# 6_Button_Array.net
KiCad netlist of a schematic drawn in EAGLE
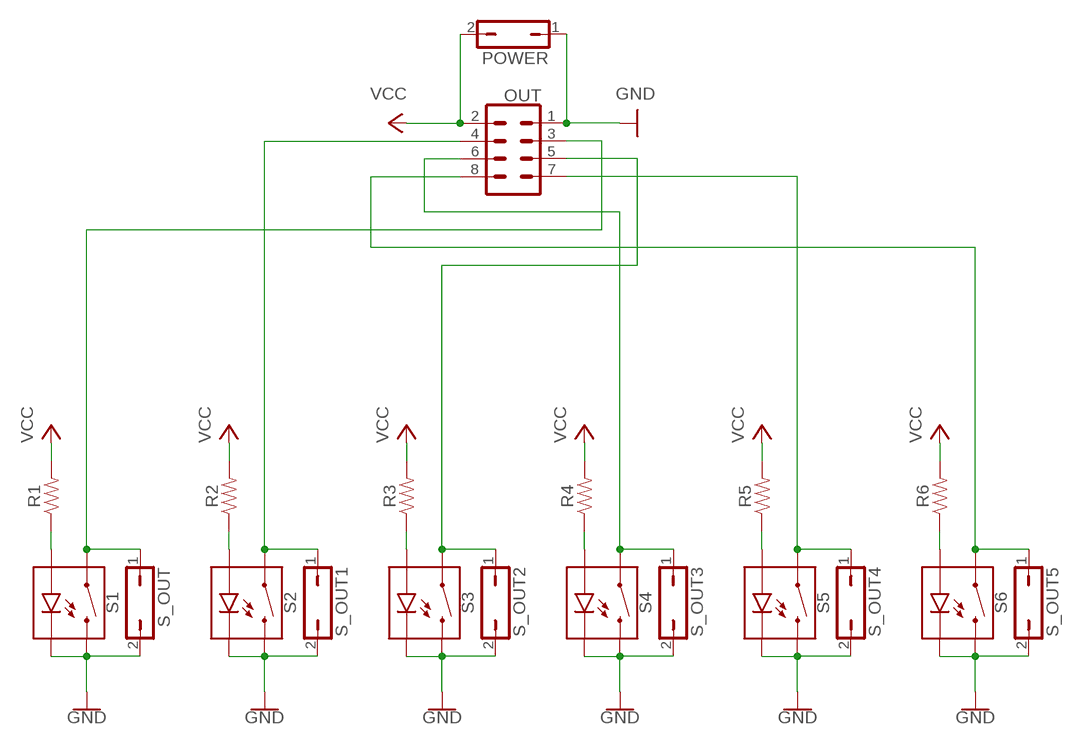
[diagram p0: schematic, sheet 1]

(export (version "E")
  (design (tool "Eeschema 10.0.6"))
  (components
    (comp (ref "OUT")
      (value "CONN_04X2")
      (footprint "eagle-import:2X4")
      (libsource (lib "eagle-import") (part "CONN_04X2"))
    )
    (comp (ref "POWER")
      (value "JP1Q")
      (footprint "eagle-import:JP1")
      (libsource (lib "eagle-import") (part "JP1Q"))
    )
    (comp (ref "R1")
      (value "RESISTOR1206")
      (footprint "eagle-import:1206")
      (libsource (lib "eagle-import") (part "RESISTOR1206"))
    )
    (comp (ref "R2")
      (value "RESISTOR1206")
      (footprint "eagle-import:1206")
      (libsource (lib "eagle-import") (part "RESISTOR1206"))
    )
    (comp (ref "R3")
      (value "RESISTOR1206")
      (footprint "eagle-import:1206")
      (libsource (lib "eagle-import") (part "RESISTOR1206"))
    )
    (comp (ref "R4")
      (value "RESISTOR1206")
      (footprint "eagle-import:1206")
      (libsource (lib "eagle-import") (part "RESISTOR1206"))
    )
    (comp (ref "R5")
      (value "RESISTOR1206")
      (footprint "eagle-import:1206")
      (libsource (lib "eagle-import") (part "RESISTOR1206"))
    )
    (comp (ref "R6")
      (value "RESISTOR1206")
      (footprint "eagle-import:1206")
      (libsource (lib "eagle-import") (part "RESISTOR1206"))
    )
    (comp (ref "S1")
      (value "MOMENTARY-SWITCH-SPST-LED-PTH-12MM")
      (footprint "eagle-import:TACTILE_SWITCH_LED_PTH_12MM")
      (libsource (lib "eagle-import") (part "MOMENTARY-SWITCH-SPST-LED-PTH-12MM"))
    )
    (comp (ref "S2")
      (value "MOMENTARY-SWITCH-SPST-LED-PTH-12MM")
      (footprint "eagle-import:TACTILE_SWITCH_LED_PTH_12MM")
      (libsource (lib "eagle-import") (part "MOMENTARY-SWITCH-SPST-LED-PTH-12MM"))
    )
    (comp (ref "S3")
      (value "MOMENTARY-SWITCH-SPST-LED-PTH-12MM")
      (footprint "eagle-import:TACTILE_SWITCH_LED_PTH_12MM")
      (libsource (lib "eagle-import") (part "MOMENTARY-SWITCH-SPST-LED-PTH-12MM"))
    )
    (comp (ref "S4")
      (value "MOMENTARY-SWITCH-SPST-LED-PTH-12MM")
      (footprint "eagle-import:TACTILE_SWITCH_LED_PTH_12MM")
      (libsource (lib "eagle-import") (part "MOMENTARY-SWITCH-SPST-LED-PTH-12MM"))
    )
    (comp (ref "S5")
      (value "MOMENTARY-SWITCH-SPST-LED-PTH-12MM")
      (footprint "eagle-import:TACTILE_SWITCH_LED_PTH_12MM")
      (libsource (lib "eagle-import") (part "MOMENTARY-SWITCH-SPST-LED-PTH-12MM"))
    )
    (comp (ref "S6")
      (value "MOMENTARY-SWITCH-SPST-LED-PTH-12MM")
      (footprint "eagle-import:TACTILE_SWITCH_LED_PTH_12MM")
      (libsource (lib "eagle-import") (part "MOMENTARY-SWITCH-SPST-LED-PTH-12MM"))
    )
    (comp (ref "S_OUT")
      (value "JP1Q")
      (footprint "eagle-import:JP1")
      (libsource (lib "eagle-import") (part "JP1Q"))
    )
    (comp (ref "S_OUT1")
      (value "JP1Q")
      (footprint "eagle-import:JP1")
      (libsource (lib "eagle-import") (part "JP1Q"))
    )
    (comp (ref "S_OUT2")
      (value "JP1Q")
      (footprint "eagle-import:JP1")
      (libsource (lib "eagle-import") (part "JP1Q"))
    )
    (comp (ref "S_OUT3")
      (value "JP1Q")
      (footprint "eagle-import:JP1")
      (libsource (lib "eagle-import") (part "JP1Q"))
    )
    (comp (ref "S_OUT4")
      (value "JP1Q")
      (footprint "eagle-import:JP1")
      (libsource (lib "eagle-import") (part "JP1Q"))
    )
    (comp (ref "S_OUT5")
      (value "JP1Q")
      (footprint "eagle-import:JP1")
      (libsource (lib "eagle-import") (part "JP1Q"))
    )
  )
  (nets
    (net (code "1") (name "GND") (class "Default")
      (node (ref "OUT") (pin "1") (pinfunction "1_1") (pintype "passive"))
      (node (ref "POWER") (pin "1") (pinfunction "1_1") (pintype "passive"))
      (node (ref "S1") (pin "2") (pinfunction "2_2") (pintype "passive"))
      (node (ref "S1") (pin "C") (pinfunction "C_C") (pintype "passive"))
      (node (ref "S2") (pin "2") (pinfunction "2_2") (pintype "passive"))
      (node (ref "S2") (pin "C") (pinfunction "C_C") (pintype "passive"))
      (node (ref "S3") (pin "2") (pinfunction "2_2") (pintype "passive"))
      (node (ref "S3") (pin "C") (pinfunction "C_C") (pintype "passive"))
      (node (ref "S4") (pin "2") (pinfunction "2_2") (pintype "passive"))
      (node (ref "S4") (pin "C") (pinfunction "C_C") (pintype "passive"))
      (node (ref "S5") (pin "2") (pinfunction "2_2") (pintype "passive"))
      (node (ref "S5") (pin "C") (pinfunction "C_C") (pintype "passive"))
      (node (ref "S6") (pin "2") (pinfunction "2_2") (pintype "passive"))
      (node (ref "S6") (pin "C") (pinfunction "C_C") (pintype "passive"))
      (node (ref "S_OUT") (pin "2") (pinfunction "2_2") (pintype "passive"))
      (node (ref "S_OUT1") (pin "2") (pinfunction "2_2") (pintype "passive"))
      (node (ref "S_OUT2") (pin "2") (pinfunction "2_2") (pintype "passive"))
      (node (ref "S_OUT3") (pin "2") (pinfunction "2_2") (pintype "passive"))
      (node (ref "S_OUT4") (pin "2") (pinfunction "2_2") (pintype "passive"))
      (node (ref "S_OUT5") (pin "2") (pinfunction "2_2") (pintype "passive"))
    )
    (net (code "2") (name "Net-(R1-Pad1)") (class "Default")
      (node (ref "R1") (pin "1") (pinfunction "1_1") (pintype "passive"))
      (node (ref "S1") (pin "A") (pinfunction "A_A") (pintype "passive"))
    )
    (net (code "3") (name "Net-(R2-Pad1)") (class "Default")
      (node (ref "R2") (pin "1") (pinfunction "1_1") (pintype "passive"))
      (node (ref "S2") (pin "A") (pinfunction "A_A") (pintype "passive"))
    )
    (net (code "4") (name "Net-(R3-Pad1)") (class "Default")
      (node (ref "R3") (pin "1") (pinfunction "1_1") (pintype "passive"))
      (node (ref "S3") (pin "A") (pinfunction "A_A") (pintype "passive"))
    )
    (net (code "5") (name "Net-(R4-Pad1)") (class "Default")
      (node (ref "R4") (pin "1") (pinfunction "1_1") (pintype "passive"))
      (node (ref "S4") (pin "A") (pinfunction "A_A") (pintype "passive"))
    )
    (net (code "6") (name "Net-(R5-Pad1)") (class "Default")
      (node (ref "R5") (pin "1") (pinfunction "1_1") (pintype "passive"))
      (node (ref "S5") (pin "A") (pinfunction "A_A") (pintype "passive"))
    )
    (net (code "7") (name "Net-(R6-Pad1)") (class "Default")
      (node (ref "R6") (pin "1") (pinfunction "1_1") (pintype "passive"))
      (node (ref "S6") (pin "A") (pinfunction "A_A") (pintype "passive"))
    )
    (net (code "8") (name "Net-(S1-1)") (class "Default")
      (node (ref "OUT") (pin "3") (pinfunction "3_3") (pintype "passive"))
      (node (ref "S1") (pin "4") (pinfunction "1_4") (pintype "passive"))
      (node (ref "S_OUT") (pin "1") (pinfunction "1_1") (pintype "passive"))
    )
    (net (code "9") (name "Net-(S2-1)") (class "Default")
      (node (ref "OUT") (pin "4") (pinfunction "4_4") (pintype "passive"))
      (node (ref "S2") (pin "4") (pinfunction "1_4") (pintype "passive"))
      (node (ref "S_OUT1") (pin "1") (pinfunction "1_1") (pintype "passive"))
    )
    (net (code "10") (name "Net-(S3-1)") (class "Default")
      (node (ref "OUT") (pin "5") (pinfunction "5_5") (pintype "passive"))
      (node (ref "S3") (pin "4") (pinfunction "1_4") (pintype "passive"))
      (node (ref "S_OUT2") (pin "1") (pinfunction "1_1") (pintype "passive"))
    )
    (net (code "11") (name "Net-(S4-1)") (class "Default")
      (node (ref "OUT") (pin "6") (pinfunction "6_6") (pintype "passive"))
      (node (ref "S4") (pin "4") (pinfunction "1_4") (pintype "passive"))
      (node (ref "S_OUT3") (pin "1") (pinfunction "1_1") (pintype "passive"))
    )
    (net (code "12") (name "Net-(S5-1)") (class "Default")
      (node (ref "OUT") (pin "7") (pinfunction "7_7") (pintype "passive"))
      (node (ref "S5") (pin "4") (pinfunction "1_4") (pintype "passive"))
      (node (ref "S_OUT4") (pin "1") (pinfunction "1_1") (pintype "passive"))
    )
    (net (code "13") (name "Net-(S6-1)") (class "Default")
      (node (ref "OUT") (pin "8") (pinfunction "8_8") (pintype "passive"))
      (node (ref "S6") (pin "4") (pinfunction "1_4") (pintype "passive"))
      (node (ref "S_OUT5") (pin "1") (pinfunction "1_1") (pintype "passive"))
    )
    (net (code "14") (name "VCC") (class "Default")
      (node (ref "OUT") (pin "2") (pinfunction "2_2") (pintype "passive"))
      (node (ref "POWER") (pin "2") (pinfunction "2_2") (pintype "passive"))
      (node (ref "R1") (pin "2") (pinfunction "2_2") (pintype "passive"))
      (node (ref "R2") (pin "2") (pinfunction "2_2") (pintype "passive"))
      (node (ref "R3") (pin "2") (pinfunction "2_2") (pintype "passive"))
      (node (ref "R4") (pin "2") (pinfunction "2_2") (pintype "passive"))
      (node (ref "R5") (pin "2") (pinfunction "2_2") (pintype "passive"))
      (node (ref "R6") (pin "2") (pinfunction "2_2") (pintype "passive"))
    )
  )
)
